# QuantumPCB_V1_0.net
KiCad netlist of a schematic drawn in EAGLE
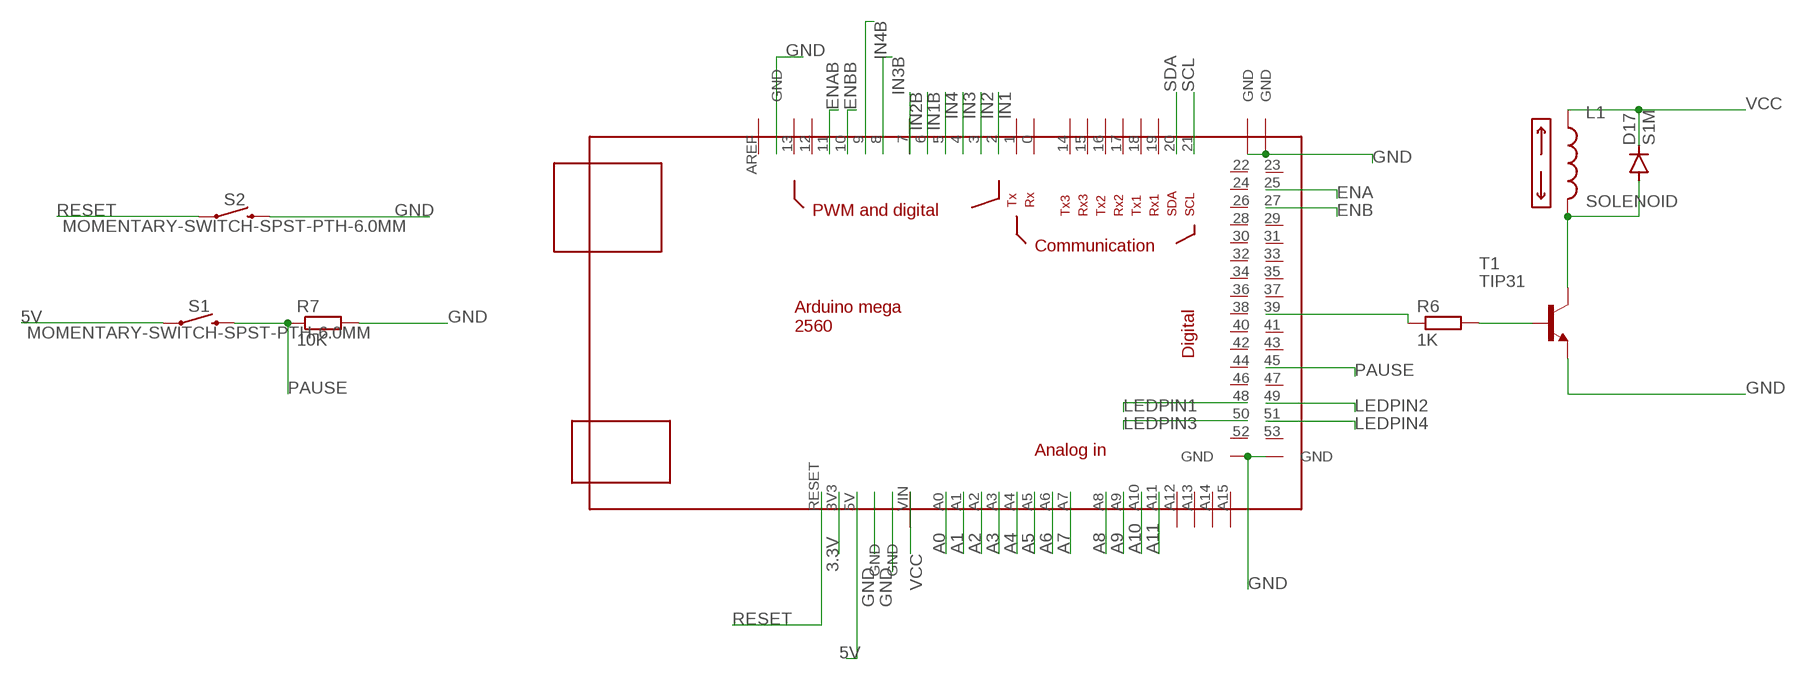
[diagram p0: schematic, sheet 1]
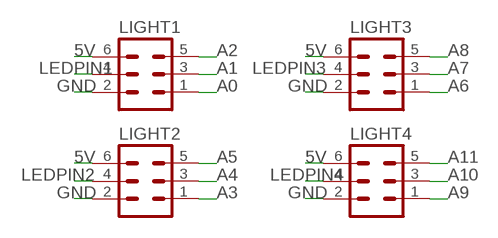
[diagram p1: schematic, sheet 2]
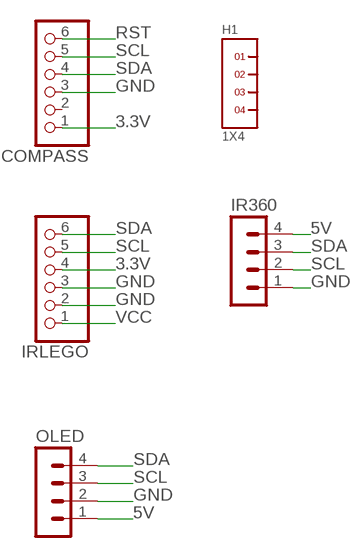
[diagram p2: schematic, sheet 3]
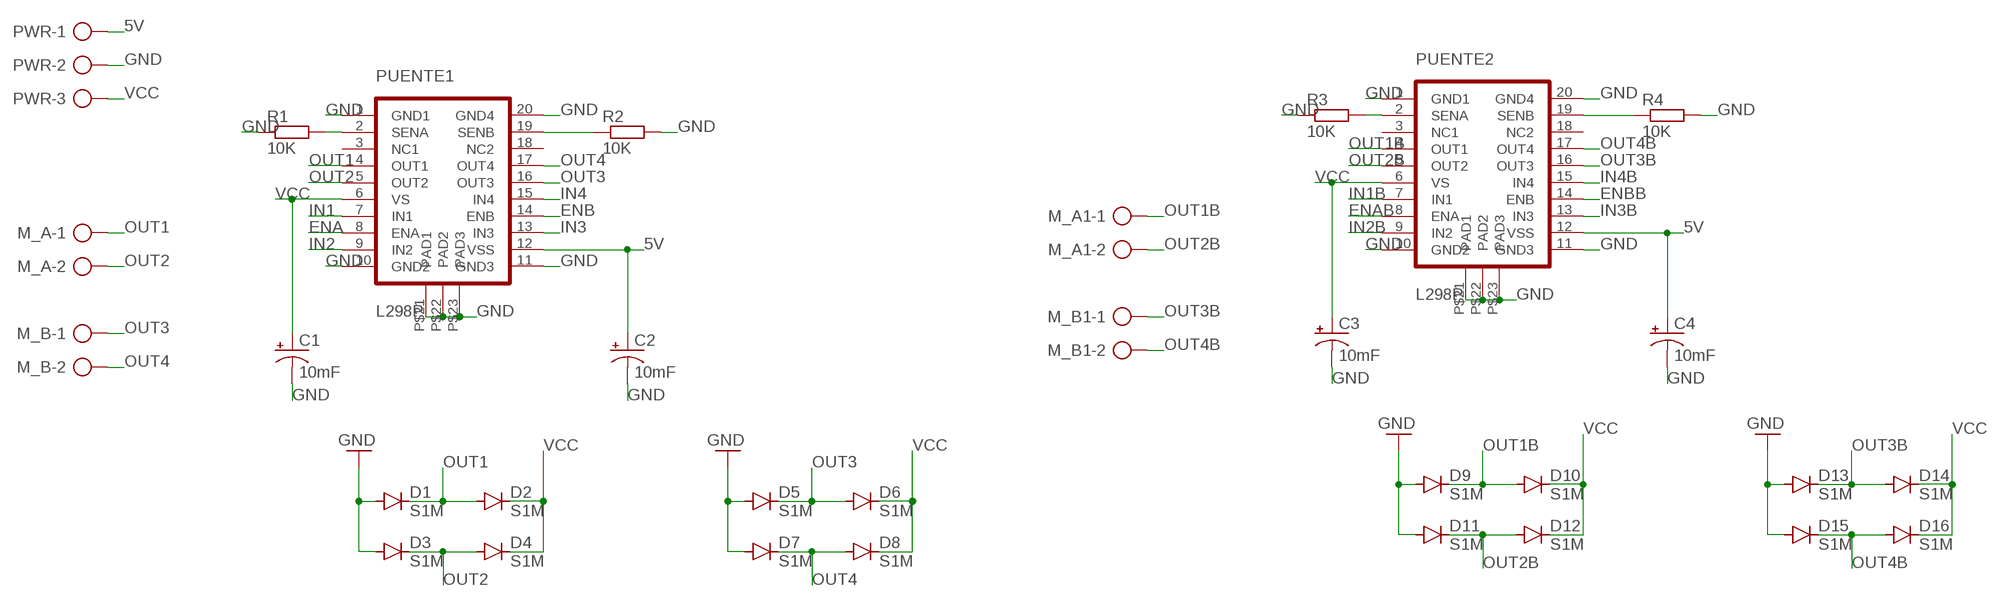
[diagram p3: schematic, sheet 4]

(export (version "E")
  (design (tool "Eeschema 10.0.6"))
  (components
    (comp (ref "D17")
      (value "S1M")
      (footprint "eagle-import:SMA")
      (libsource (lib "eagle-import") (part "S1M"))
    )
    (comp (ref "L1")
      (value "SOLENOID")
      (footprint "eagle-import:1X02")
      (libsource (lib "eagle-import") (part "SOLENOID"))
    )
    (comp (ref "R6")
      (value "1K")
      (footprint "eagle-import:R0603")
      (libsource (lib "eagle-import") (part "R-EU_R0603"))
    )
    (comp (ref "R7")
      (value "10K")
      (footprint "eagle-import:R0603")
      (libsource (lib "eagle-import") (part "R-EU_R0603"))
    )
    (comp (ref "S1")
      (value "MOMENTARY-SWITCH-SPST-PTH-6.0MM")
      (footprint "eagle-import:TACTILE_SWITCH_PTH_6.0MM")
      (libsource (lib "eagle-import") (part "MOMENTARY-SWITCH-SPST-PTH-6.0MM"))
    )
    (comp (ref "S2")
      (value "MOMENTARY-SWITCH-SPST-PTH-6.0MM")
      (footprint "eagle-import:TACTILE_SWITCH_PTH_6.0MM")
      (libsource (lib "eagle-import") (part "MOMENTARY-SWITCH-SPST-PTH-6.0MM"))
    )
    (comp (ref "T1")
      (value "TIP31")
      (footprint "eagle-import:TO220")
      (libsource (lib "eagle-import") (part "TIP31"))
    )
    (comp (ref "U$1")
      (value "MEGA_DEVICE")
      (footprint "eagle-import:MEGAOUTLINE")
      (libsource (lib "eagle-import") (part "MEGA_DEVICE"))
    )
    (comp (ref "C1")
      (value "10mF")
      (footprint "eagle-import:E2-5")
      (libsource (lib "eagle-import") (part "CPOL-USE2-5"))
    )
    (comp (ref "C2")
      (value "10mF")
      (footprint "eagle-import:E2-5")
      (libsource (lib "eagle-import") (part "CPOL-USE2-5"))
    )
    (comp (ref "C3")
      (value "10mF")
      (footprint "eagle-import:E2-5")
      (libsource (lib "eagle-import") (part "CPOL-USE2-5"))
    )
    (comp (ref "C4")
      (value "10mF")
      (footprint "eagle-import:E2-5")
      (libsource (lib "eagle-import") (part "CPOL-USE2-5"))
    )
    (comp (ref "D1")
      (value "S1M")
      (footprint "eagle-import:SMA")
      (libsource (lib "eagle-import") (part "S1M"))
    )
    (comp (ref "D2")
      (value "S1M")
      (footprint "eagle-import:SMA")
      (libsource (lib "eagle-import") (part "S1M"))
    )
    (comp (ref "D3")
      (value "S1M")
      (footprint "eagle-import:SMA")
      (libsource (lib "eagle-import") (part "S1M"))
    )
    (comp (ref "D4")
      (value "S1M")
      (footprint "eagle-import:SMA")
      (libsource (lib "eagle-import") (part "S1M"))
    )
    (comp (ref "D5")
      (value "S1M")
      (footprint "eagle-import:SMA")
      (libsource (lib "eagle-import") (part "S1M"))
    )
    (comp (ref "D6")
      (value "S1M")
      (footprint "eagle-import:SMA")
      (libsource (lib "eagle-import") (part "S1M"))
    )
    (comp (ref "D7")
      (value "S1M")
      (footprint "eagle-import:SMA")
      (libsource (lib "eagle-import") (part "S1M"))
    )
    (comp (ref "D8")
      (value "S1M")
      (footprint "eagle-import:SMA")
      (libsource (lib "eagle-import") (part "S1M"))
    )
    (comp (ref "D9")
      (value "S1M")
      (footprint "eagle-import:SMA")
      (libsource (lib "eagle-import") (part "S1M"))
    )
    (comp (ref "D10")
      (value "S1M")
      (footprint "eagle-import:SMA")
      (libsource (lib "eagle-import") (part "S1M"))
    )
    (comp (ref "D11")
      (value "S1M")
      (footprint "eagle-import:SMA")
      (libsource (lib "eagle-import") (part "S1M"))
    )
    (comp (ref "D12")
      (value "S1M")
      (footprint "eagle-import:SMA")
      (libsource (lib "eagle-import") (part "S1M"))
    )
    (comp (ref "D13")
      (value "S1M")
      (footprint "eagle-import:SMA")
      (libsource (lib "eagle-import") (part "S1M"))
    )
    (comp (ref "D14")
      (value "S1M")
      (footprint "eagle-import:SMA")
      (libsource (lib "eagle-import") (part "S1M"))
    )
    (comp (ref "D15")
      (value "S1M")
      (footprint "eagle-import:SMA")
      (libsource (lib "eagle-import") (part "S1M"))
    )
    (comp (ref "D16")
      (value "S1M")
      (footprint "eagle-import:SMA")
      (libsource (lib "eagle-import") (part "S1M"))
    )
    (comp (ref "M_A")
      (value "AK500/2")
      (footprint "eagle-import:AK500_2")
      (libsource (lib "eagle-import") (part "AK500/2"))
    )
    (comp (ref "M_A1")
      (value "AK500/2")
      (footprint "eagle-import:AK500_2")
      (libsource (lib "eagle-import") (part "AK500/2"))
    )
    (comp (ref "M_B")
      (value "AK500/2")
      (footprint "eagle-import:AK500_2")
      (libsource (lib "eagle-import") (part "AK500/2"))
    )
    (comp (ref "M_B1")
      (value "AK500/2")
      (footprint "eagle-import:AK500_2")
      (libsource (lib "eagle-import") (part "AK500/2"))
    )
    (comp (ref "PUENTE1")
      (value "L298P")
      (footprint "eagle-import:POWER-SO20")
      (fields (field (name "MF") "STMicroelectronics"))
      (libsource (lib "eagle-import") (part "L298P"))
    )
    (comp (ref "PUENTE2")
      (value "L298P")
      (footprint "eagle-import:POWER-SO20")
      (fields (field (name "MF") "STMicroelectronics"))
      (libsource (lib "eagle-import") (part "L298P"))
    )
    (comp (ref "PWR")
      (value "AK500/3")
      (footprint "eagle-import:AK500_3")
      (libsource (lib "eagle-import") (part "AK500/3"))
    )
    (comp (ref "R1")
      (value "10K")
      (footprint "eagle-import:R0603")
      (libsource (lib "eagle-import") (part "R-EU_R0603"))
    )
    (comp (ref "R2")
      (value "10K")
      (footprint "eagle-import:R0603")
      (libsource (lib "eagle-import") (part "R-EU_R0603"))
    )
    (comp (ref "R3")
      (value "10K")
      (footprint "eagle-import:R0603")
      (libsource (lib "eagle-import") (part "R-EU_R0603"))
    )
    (comp (ref "R4")
      (value "10K")
      (footprint "eagle-import:R0603")
      (libsource (lib "eagle-import") (part "R-EU_R0603"))
    )
    (comp (ref "LIGHT1")
      (value "MA03-2")
      (footprint "eagle-import:MA03-2")
      (libsource (lib "eagle-import") (part "MA03-2"))
    )
    (comp (ref "LIGHT2")
      (value "MA03-2")
      (footprint "eagle-import:MA03-2")
      (libsource (lib "eagle-import") (part "MA03-2"))
    )
    (comp (ref "LIGHT3")
      (value "MA03-2")
      (footprint "eagle-import:MA03-2")
      (libsource (lib "eagle-import") (part "MA03-2"))
    )
    (comp (ref "LIGHT4")
      (value "MA03-2")
      (footprint "eagle-import:MA03-2")
      (libsource (lib "eagle-import") (part "MA03-2"))
    )
    (comp (ref "COMPASS")
      (value "PINHD-1X6")
      (footprint "eagle-import:1X06")
      (libsource (lib "eagle-import") (part "PINHD-1X6"))
    )
    (comp (ref "H1")
      (value "1X4")
      (footprint "eagle-import:1X4")
      (libsource (lib "eagle-import") (part "1X4"))
    )
    (comp (ref "IR360")
      (value "MA04-1")
      (footprint "eagle-import:MA04-1")
      (libsource (lib "eagle-import") (part "MA04-1"))
    )
    (comp (ref "IRLEGO")
      (value "PINHD-1X6")
      (footprint "eagle-import:1X06")
      (libsource (lib "eagle-import") (part "PINHD-1X6"))
    )
    (comp (ref "OLED")
      (value "MA04-1")
      (footprint "eagle-import:MA04-1")
      (libsource (lib "eagle-import") (part "MA04-1"))
    )
  )
  (nets
    (net (code "1") (name "3.3V") (class "Default")
      (node (ref "COMPASS") (pin "1") (pinfunction "1_1") (pintype "passive"))
      (node (ref "IRLEGO") (pin "4") (pinfunction "4_4") (pintype "passive"))
      (node (ref "U$1") (pin "3V3") (pinfunction "3V3_3V3") (pintype "bidirectional"))
    )
    (net (code "2") (name "5V") (class "Default")
      (node (ref "C2") (pin "+") (pinfunction "+_+") (pintype "passive"))
      (node (ref "C4") (pin "+") (pinfunction "+_+") (pintype "passive"))
      (node (ref "IR360") (pin "4") (pinfunction "4_4") (pintype "passive"))
      (node (ref "LIGHT1") (pin "6") (pinfunction "6_6") (pintype "passive"))
      (node (ref "LIGHT2") (pin "6") (pinfunction "6_6") (pintype "passive"))
      (node (ref "LIGHT3") (pin "6") (pinfunction "6_6") (pintype "passive"))
      (node (ref "LIGHT4") (pin "6") (pinfunction "6_6") (pintype "passive"))
      (node (ref "OLED") (pin "1") (pinfunction "1_1") (pintype "passive"))
      (node (ref "PUENTE1") (pin "P$12") (pinfunction "VSS_P$12") (pintype "power_in"))
      (node (ref "PUENTE2") (pin "P$12") (pinfunction "VSS_P$12") (pintype "power_in"))
      (node (ref "PWR") (pin "1") (pinfunction "KL_1") (pintype "passive"))
      (node (ref "S1") (pin "1") (pinfunction "1_1") (pintype "passive"))
      (node (ref "U$1") (pin "5V") (pinfunction "5V_5V") (pintype "bidirectional"))
    )
    (net (code "3") (name "A0") (class "Default")
      (node (ref "LIGHT1") (pin "1") (pinfunction "1_1") (pintype "passive"))
      (node (ref "U$1") (pin "A0") (pinfunction "A0_A0") (pintype "bidirectional"))
    )
    (net (code "4") (name "A1") (class "Default")
      (node (ref "LIGHT1") (pin "3") (pinfunction "3_3") (pintype "passive"))
      (node (ref "U$1") (pin "A1") (pinfunction "A1_A1") (pintype "bidirectional"))
    )
    (net (code "5") (name "A2") (class "Default")
      (node (ref "LIGHT1") (pin "5") (pinfunction "5_5") (pintype "passive"))
      (node (ref "U$1") (pin "A2") (pinfunction "A2_A2") (pintype "bidirectional"))
    )
    (net (code "6") (name "A3") (class "Default")
      (node (ref "LIGHT2") (pin "1") (pinfunction "1_1") (pintype "passive"))
      (node (ref "U$1") (pin "A3") (pinfunction "A3_A3") (pintype "bidirectional"))
    )
    (net (code "7") (name "A4") (class "Default")
      (node (ref "LIGHT2") (pin "3") (pinfunction "3_3") (pintype "passive"))
      (node (ref "U$1") (pin "A4") (pinfunction "A4_A4") (pintype "bidirectional"))
    )
    (net (code "8") (name "A5") (class "Default")
      (node (ref "LIGHT2") (pin "5") (pinfunction "5_5") (pintype "passive"))
      (node (ref "U$1") (pin "A5") (pinfunction "A5_A5") (pintype "bidirectional"))
    )
    (net (code "9") (name "A6") (class "Default")
      (node (ref "LIGHT3") (pin "1") (pinfunction "1_1") (pintype "passive"))
      (node (ref "U$1") (pin "A6") (pinfunction "A6_A6") (pintype "bidirectional"))
    )
    (net (code "10") (name "A7") (class "Default")
      (node (ref "LIGHT3") (pin "3") (pinfunction "3_3") (pintype "passive"))
      (node (ref "U$1") (pin "A7") (pinfunction "A7_A7") (pintype "bidirectional"))
    )
    (net (code "11") (name "A8") (class "Default")
      (node (ref "LIGHT3") (pin "5") (pinfunction "5_5") (pintype "passive"))
      (node (ref "U$1") (pin "A8") (pinfunction "A8_A8") (pintype "bidirectional"))
    )
    (net (code "12") (name "A9") (class "Default")
      (node (ref "LIGHT4") (pin "1") (pinfunction "1_1") (pintype "passive"))
      (node (ref "U$1") (pin "A9") (pinfunction "A9_A9") (pintype "bidirectional"))
    )
    (net (code "13") (name "A10") (class "Default")
      (node (ref "LIGHT4") (pin "3") (pinfunction "3_3") (pintype "passive"))
      (node (ref "U$1") (pin "A10") (pinfunction "A10_A10") (pintype "bidirectional"))
    )
    (net (code "14") (name "A11") (class "Default")
      (node (ref "LIGHT4") (pin "5") (pinfunction "5_5") (pintype "passive"))
      (node (ref "U$1") (pin "A11") (pinfunction "A11_A11") (pintype "bidirectional"))
    )
    (net (code "15") (name "ENA") (class "Default")
      (node (ref "PUENTE1") (pin "P$8") (pinfunction "ENA_P$8") (pintype "input"))
      (node (ref "U$1") (pin "25") (pinfunction "25_25") (pintype "bidirectional"))
    )
    (net (code "16") (name "ENAB") (class "Default")
      (node (ref "PUENTE2") (pin "P$8") (pinfunction "ENA_P$8") (pintype "input"))
      (node (ref "U$1") (pin "11") (pinfunction "11_11") (pintype "bidirectional"))
    )
    (net (code "17") (name "ENB") (class "Default")
      (node (ref "PUENTE1") (pin "P$14") (pinfunction "ENB_P$14") (pintype "input"))
      (node (ref "U$1") (pin "27") (pinfunction "27_27") (pintype "bidirectional"))
    )
    (net (code "18") (name "ENBB") (class "Default")
      (node (ref "PUENTE2") (pin "P$14") (pinfunction "ENB_P$14") (pintype "input"))
      (node (ref "U$1") (pin "10") (pinfunction "10_10") (pintype "bidirectional"))
    )
    (net (code "19") (name "GND") (class "Default")
      (node (ref "C1") (pin "-") (pinfunction "-_-") (pintype "passive"))
      (node (ref "C2") (pin "-") (pinfunction "-_-") (pintype "passive"))
      (node (ref "C3") (pin "-") (pinfunction "-_-") (pintype "passive"))
      (node (ref "C4") (pin "-") (pinfunction "-_-") (pintype "passive"))
      (node (ref "COMPASS") (pin "3") (pinfunction "3_3") (pintype "passive"))
      (node (ref "D1") (pin "A") (pinfunction "A_A") (pintype "passive"))
      (node (ref "D11") (pin "A") (pinfunction "A_A") (pintype "passive"))
      (node (ref "D13") (pin "A") (pinfunction "A_A") (pintype "passive"))
      (node (ref "D15") (pin "A") (pinfunction "A_A") (pintype "passive"))
      (node (ref "D3") (pin "A") (pinfunction "A_A") (pintype "passive"))
      (node (ref "D5") (pin "A") (pinfunction "A_A") (pintype "passive"))
      (node (ref "D7") (pin "A") (pinfunction "A_A") (pintype "passive"))
      (node (ref "D9") (pin "A") (pinfunction "A_A") (pintype "passive"))
      (node (ref "IR360") (pin "1") (pinfunction "1_1") (pintype "passive"))
      (node (ref "IRLEGO") (pin "2") (pinfunction "2_2") (pintype "passive"))
      (node (ref "IRLEGO") (pin "3") (pinfunction "3_3") (pintype "passive"))
      (node (ref "LIGHT1") (pin "2") (pinfunction "2_2") (pintype "passive"))
      (node (ref "LIGHT2") (pin "2") (pinfunction "2_2") (pintype "passive"))
      (node (ref "LIGHT3") (pin "2") (pinfunction "2_2") (pintype "passive"))
      (node (ref "LIGHT4") (pin "2") (pinfunction "2_2") (pintype "passive"))
      (node (ref "OLED") (pin "2") (pinfunction "2_2") (pintype "passive"))
      (node (ref "PUENTE1") (pin "P$1") (pinfunction "GND1_P$1") (pintype "power_in"))
      (node (ref "PUENTE1") (pin "P$10") (pinfunction "GND2_P$10") (pintype "power_in"))
      (node (ref "PUENTE1") (pin "P$11") (pinfunction "GND3_P$11") (pintype "power_in"))
      (node (ref "PUENTE1") (pin "P$20") (pinfunction "GND4_P$20") (pintype "power_in"))
      (node (ref "PUENTE1") (pin "P$21") (pinfunction "PAD1_P$21") (pintype "passive"))
      (node (ref "PUENTE1") (pin "P$22") (pinfunction "PAD2_P$22") (pintype "passive"))
      (node (ref "PUENTE1") (pin "P$23") (pinfunction "PAD3_P$23") (pintype "passive"))
      (node (ref "PUENTE2") (pin "P$1") (pinfunction "GND1_P$1") (pintype "power_in"))
      (node (ref "PUENTE2") (pin "P$10") (pinfunction "GND2_P$10") (pintype "power_in"))
      (node (ref "PUENTE2") (pin "P$11") (pinfunction "GND3_P$11") (pintype "power_in"))
      (node (ref "PUENTE2") (pin "P$20") (pinfunction "GND4_P$20") (pintype "power_in"))
      (node (ref "PUENTE2") (pin "P$21") (pinfunction "PAD1_P$21") (pintype "passive"))
      (node (ref "PUENTE2") (pin "P$22") (pinfunction "PAD2_P$22") (pintype "passive"))
      (node (ref "PUENTE2") (pin "P$23") (pinfunction "PAD3_P$23") (pintype "passive"))
      (node (ref "PWR") (pin "2") (pinfunction "KL_2") (pintype "passive"))
      (node (ref "R1") (pin "1") (pinfunction "1_1") (pintype "passive"))
      (node (ref "R2") (pin "2") (pinfunction "2_2") (pintype "passive"))
      (node (ref "R3") (pin "1") (pinfunction "1_1") (pintype "passive"))
      (node (ref "R4") (pin "2") (pinfunction "2_2") (pintype "passive"))
      (node (ref "R7") (pin "2") (pinfunction "2_2") (pintype "passive"))
      (node (ref "S2") (pin "3") (pinfunction "2_3") (pintype "passive"))
      (node (ref "T1") (pin "3") (pinfunction "E_3") (pintype "passive"))
      (node (ref "U$1") (pin "GND@1") (pinfunction "GND_GND@1") (pintype "bidirectional"))
      (node (ref "U$1") (pin "GND@2") (pinfunction "GND_GND@2") (pintype "bidirectional"))
      (node (ref "U$1") (pin "GND@3") (pinfunction "GND_GND@3") (pintype "bidirectional"))
      (node (ref "U$1") (pin "GND@4") (pinfunction "GND_GND@4") (pintype "bidirectional"))
      (node (ref "U$1") (pin "GND@5") (pinfunction "GND_GND@5") (pintype "bidirectional"))
      (node (ref "U$1") (pin "GND@6") (pinfunction "GND_GND@6") (pintype "bidirectional"))
      (node (ref "U$1") (pin "GND@7") (pinfunction "GND_GND@7") (pintype "bidirectional"))
    )
    (net (code "20") (name "IN1") (class "Default")
      (node (ref "PUENTE1") (pin "P$7") (pinfunction "IN1_P$7") (pintype "input"))
      (node (ref "U$1") (pin "2") (pinfunction "2_2") (pintype "bidirectional"))
    )
    (net (code "21") (name "IN1B") (class "Default")
      (node (ref "PUENTE2") (pin "P$7") (pinfunction "IN1_P$7") (pintype "input"))
      (node (ref "U$1") (pin "6") (pinfunction "6_6") (pintype "bidirectional"))
    )
    (net (code "22") (name "IN2") (class "Default")
      (node (ref "PUENTE1") (pin "P$9") (pinfunction "IN2_P$9") (pintype "input"))
      (node (ref "U$1") (pin "3") (pinfunction "3_3") (pintype "bidirectional"))
    )
    (net (code "23") (name "IN2B") (class "Default")
      (node (ref "PUENTE2") (pin "P$9") (pinfunction "IN2_P$9") (pintype "input"))
      (node (ref "U$1") (pin "7") (pinfunction "7_7") (pintype "bidirectional"))
    )
    (net (code "24") (name "IN3") (class "Default")
      (node (ref "PUENTE1") (pin "P$13") (pinfunction "IN3_P$13") (pintype "input"))
      (node (ref "U$1") (pin "4") (pinfunction "4_4") (pintype "bidirectional"))
    )
    (net (code "25") (name "IN3B") (class "Default")
      (node (ref "PUENTE2") (pin "P$13") (pinfunction "IN3_P$13") (pintype "input"))
      (node (ref "U$1") (pin "8") (pinfunction "8_8") (pintype "bidirectional"))
    )
    (net (code "26") (name "IN4") (class "Default")
      (node (ref "PUENTE1") (pin "P$15") (pinfunction "IN4_P$15") (pintype "input"))
      (node (ref "U$1") (pin "5") (pinfunction "5_5") (pintype "bidirectional"))
    )
    (net (code "27") (name "IN4B") (class "Default")
      (node (ref "PUENTE2") (pin "P$15") (pinfunction "IN4_P$15") (pintype "input"))
      (node (ref "U$1") (pin "9") (pinfunction "9_9") (pintype "bidirectional"))
    )
    (net (code "28") (name "LEDPIN1") (class "Default")
      (node (ref "LIGHT1") (pin "4") (pinfunction "4_4") (pintype "passive"))
      (node (ref "U$1") (pin "48") (pinfunction "48_48") (pintype "bidirectional"))
    )
    (net (code "29") (name "LEDPIN2") (class "Default")
      (node (ref "LIGHT2") (pin "4") (pinfunction "4_4") (pintype "passive"))
      (node (ref "U$1") (pin "49") (pinfunction "49_49") (pintype "bidirectional"))
    )
    (net (code "30") (name "LEDPIN3") (class "Default")
      (node (ref "LIGHT3") (pin "4") (pinfunction "4_4") (pintype "passive"))
      (node (ref "U$1") (pin "50") (pinfunction "50_50") (pintype "bidirectional"))
    )
    (net (code "31") (name "LEDPIN4") (class "Default")
      (node (ref "LIGHT4") (pin "4") (pinfunction "4_4") (pintype "passive"))
      (node (ref "U$1") (pin "51") (pinfunction "51_51") (pintype "bidirectional"))
    )
    (net (code "32") (name "Net-(PUENTE1-SENA)") (class "Default")
      (node (ref "PUENTE1") (pin "P$2") (pinfunction "SENA_P$2") (pintype "input"))
      (node (ref "R1") (pin "2") (pinfunction "2_2") (pintype "passive"))
    )
    (net (code "33") (name "Net-(PUENTE1-SENB)") (class "Default")
      (node (ref "PUENTE1") (pin "P$19") (pinfunction "SENB_P$19") (pintype "input"))
      (node (ref "R2") (pin "1") (pinfunction "1_1") (pintype "passive"))
    )
    (net (code "34") (name "Net-(PUENTE2-SENA)") (class "Default")
      (node (ref "PUENTE2") (pin "P$2") (pinfunction "SENA_P$2") (pintype "input"))
      (node (ref "R3") (pin "2") (pinfunction "2_2") (pintype "passive"))
    )
    (net (code "35") (name "Net-(PUENTE2-SENB)") (class "Default")
      (node (ref "PUENTE2") (pin "P$19") (pinfunction "SENB_P$19") (pintype "input"))
      (node (ref "R4") (pin "1") (pinfunction "1_1") (pintype "passive"))
    )
    (net (code "36") (name "Net-(R6-Pad1)") (class "Default")
      (node (ref "R6") (pin "1") (pinfunction "1_1") (pintype "passive"))
      (node (ref "U$1") (pin "39") (pinfunction "39_39") (pintype "bidirectional"))
    )
    (net (code "37") (name "Net-(T1-B)") (class "Default")
      (node (ref "R6") (pin "2") (pinfunction "2_2") (pintype "passive"))
      (node (ref "T1") (pin "1") (pinfunction "B_1") (pintype "passive"))
    )
    (net (code "38") (name "Net-(T1-C)") (class "Default")
      (node (ref "D17") (pin "A") (pinfunction "A_A") (pintype "passive"))
      (node (ref "L1") (pin "2") (pinfunction "2_2") (pintype "passive"))
      (node (ref "T1") (pin "2") (pinfunction "C_2") (pintype "passive"))
    )
    (net (code "39") (name "OUT1") (class "Default")
      (node (ref "D1") (pin "C") (pinfunction "C_C") (pintype "passive"))
      (node (ref "D2") (pin "A") (pinfunction "A_A") (pintype "passive"))
      (node (ref "M_A") (pin "1") (pinfunction "KL_1") (pintype "passive"))
      (node (ref "PUENTE1") (pin "P$4") (pinfunction "OUT1_P$4") (pintype "output"))
    )
    (net (code "40") (name "OUT1B") (class "Default")
      (node (ref "D10") (pin "A") (pinfunction "A_A") (pintype "passive"))
      (node (ref "D9") (pin "C") (pinfunction "C_C") (pintype "passive"))
      (node (ref "M_A1") (pin "1") (pinfunction "KL_1") (pintype "passive"))
      (node (ref "PUENTE2") (pin "P$4") (pinfunction "OUT1_P$4") (pintype "output"))
    )
    (net (code "41") (name "OUT2") (class "Default")
      (node (ref "D3") (pin "C") (pinfunction "C_C") (pintype "passive"))
      (node (ref "D4") (pin "A") (pinfunction "A_A") (pintype "passive"))
      (node (ref "M_A") (pin "2") (pinfunction "KL_2") (pintype "passive"))
      (node (ref "PUENTE1") (pin "P$5") (pinfunction "OUT2_P$5") (pintype "output"))
    )
    (net (code "42") (name "OUT2B") (class "Default")
      (node (ref "D11") (pin "C") (pinfunction "C_C") (pintype "passive"))
      (node (ref "D12") (pin "A") (pinfunction "A_A") (pintype "passive"))
      (node (ref "M_A1") (pin "2") (pinfunction "KL_2") (pintype "passive"))
      (node (ref "PUENTE2") (pin "P$5") (pinfunction "OUT2_P$5") (pintype "output"))
    )
    (net (code "43") (name "OUT3") (class "Default")
      (node (ref "D5") (pin "C") (pinfunction "C_C") (pintype "passive"))
      (node (ref "D6") (pin "A") (pinfunction "A_A") (pintype "passive"))
      (node (ref "M_B") (pin "1") (pinfunction "KL_1") (pintype "passive"))
      (node (ref "PUENTE1") (pin "P$16") (pinfunction "OUT3_P$16") (pintype "output"))
    )
    (net (code "44") (name "OUT3B") (class "Default")
      (node (ref "D13") (pin "C") (pinfunction "C_C") (pintype "passive"))
      (node (ref "D14") (pin "A") (pinfunction "A_A") (pintype "passive"))
      (node (ref "M_B1") (pin "1") (pinfunction "KL_1") (pintype "passive"))
      (node (ref "PUENTE2") (pin "P$16") (pinfunction "OUT3_P$16") (pintype "output"))
    )
    (net (code "45") (name "OUT4") (class "Default")
      (node (ref "D7") (pin "C") (pinfunction "C_C") (pintype "passive"))
      (node (ref "D8") (pin "A") (pinfunction "A_A") (pintype "passive"))
      (node (ref "M_B") (pin "2") (pinfunction "KL_2") (pintype "passive"))
      (node (ref "PUENTE1") (pin "P$17") (pinfunction "OUT4_P$17") (pintype "output"))
    )
    (net (code "46") (name "OUT4B") (class "Default")
      (node (ref "D15") (pin "C") (pinfunction "C_C") (pintype "passive"))
      (node (ref "D16") (pin "A") (pinfunction "A_A") (pintype "passive"))
      (node (ref "M_B1") (pin "2") (pinfunction "KL_2") (pintype "passive"))
      (node (ref "PUENTE2") (pin "P$17") (pinfunction "OUT4_P$17") (pintype "output"))
    )
    (net (code "47") (name "PAUSE") (class "Default")
      (node (ref "R7") (pin "1") (pinfunction "1_1") (pintype "passive"))
      (node (ref "S1") (pin "3") (pinfunction "2_3") (pintype "passive"))
      (node (ref "U$1") (pin "45") (pinfunction "45_45") (pintype "bidirectional"))
    )
    (net (code "48") (name "RESET") (class "Default")
      (node (ref "S2") (pin "1") (pinfunction "1_1") (pintype "passive"))
      (node (ref "U$1") (pin "RESET") (pinfunction "RESET_RESET") (pintype "bidirectional"))
    )
    (net (code "49") (name "RST") (class "Default")
      (node (ref "COMPASS") (pin "6") (pinfunction "6_6") (pintype "passive"))
    )
    (net (code "50") (name "SCL") (class "Default")
      (node (ref "COMPASS") (pin "5") (pinfunction "5_5") (pintype "passive"))
      (node (ref "IR360") (pin "2") (pinfunction "2_2") (pintype "passive"))
      (node (ref "IRLEGO") (pin "5") (pinfunction "5_5") (pintype "passive"))
      (node (ref "OLED") (pin "3") (pinfunction "3_3") (pintype "passive"))
      (node (ref "U$1") (pin "21") (pinfunction "21_21") (pintype "bidirectional"))
    )
    (net (code "51") (name "SDA") (class "Default")
      (node (ref "COMPASS") (pin "4") (pinfunction "4_4") (pintype "passive"))
      (node (ref "IR360") (pin "3") (pinfunction "3_3") (pintype "passive"))
      (node (ref "IRLEGO") (pin "6") (pinfunction "6_6") (pintype "passive"))
      (node (ref "OLED") (pin "4") (pinfunction "4_4") (pintype "passive"))
      (node (ref "U$1") (pin "20") (pinfunction "20_20") (pintype "bidirectional"))
    )
    (net (code "52") (name "VCC") (class "Default")
      (node (ref "C1") (pin "+") (pinfunction "+_+") (pintype "passive"))
      (node (ref "C3") (pin "+") (pinfunction "+_+") (pintype "passive"))
      (node (ref "D10") (pin "C") (pinfunction "C_C") (pintype "passive"))
      (node (ref "D12") (pin "C") (pinfunction "C_C") (pintype "passive"))
      (node (ref "D14") (pin "C") (pinfunction "C_C") (pintype "passive"))
      (node (ref "D16") (pin "C") (pinfunction "C_C") (pintype "passive"))
      (node (ref "D17") (pin "C") (pinfunction "C_C") (pintype "passive"))
      (node (ref "D2") (pin "C") (pinfunction "C_C") (pintype "passive"))
      (node (ref "D4") (pin "C") (pinfunction "C_C") (pintype "passive"))
      (node (ref "D6") (pin "C") (pinfunction "C_C") (pintype "passive"))
      (node (ref "D8") (pin "C") (pinfunction "C_C") (pintype "passive"))
      (node (ref "IRLEGO") (pin "1") (pinfunction "1_1") (pintype "passive"))
      (node (ref "L1") (pin "1") (pinfunction "1_1") (pintype "passive"))
      (node (ref "PUENTE1") (pin "P$6") (pinfunction "VS_P$6") (pintype "power_in"))
      (node (ref "PUENTE2") (pin "P$6") (pinfunction "VS_P$6") (pintype "power_in"))
      (node (ref "PWR") (pin "3") (pinfunction "KL_3") (pintype "passive"))
      (node (ref "U$1") (pin "VIN") (pinfunction "VIN_VIN") (pintype "bidirectional"))
    )
    (net (code "53") (name "unconnected-(COMPASS-Pad2)") (class "Default")
      (node (ref "COMPASS") (pin "2") (pinfunction "2_2") (pintype "passive"))
    )
    (net (code "54") (name "unconnected-(H1-Pad1)") (class "Default")
      (node (ref "H1") (pin "1") (pinfunction "1_1") (pintype "bidirectional"))
    )
    (net (code "55") (name "unconnected-(H1-Pad2)") (class "Default")
      (node (ref "H1") (pin "2") (pinfunction "2_2") (pintype "bidirectional"))
    )
    (net (code "56") (name "unconnected-(H1-Pad3)") (class "Default")
      (node (ref "H1") (pin "3") (pinfunction "3_3") (pintype "bidirectional"))
    )
    (net (code "57") (name "unconnected-(H1-Pad4)") (class "Default")
      (node (ref "H1") (pin "4") (pinfunction "4_4") (pintype "bidirectional"))
    )
    (net (code "58") (name "unconnected-(PUENTE1-NC1-PadP$3)") (class "Default")
      (node (ref "PUENTE1") (pin "P$3") (pinfunction "NC1_P$3") (pintype "no_connect"))
    )
    (net (code "59") (name "unconnected-(PUENTE1-NC2-PadP$18)") (class "Default")
      (node (ref "PUENTE1") (pin "P$18") (pinfunction "NC2_P$18") (pintype "no_connect"))
    )
    (net (code "60") (name "unconnected-(PUENTE2-NC1-PadP$3)") (class "Default")
      (node (ref "PUENTE2") (pin "P$3") (pinfunction "NC1_P$3") (pintype "no_connect"))
    )
    (net (code "61") (name "unconnected-(PUENTE2-NC2-PadP$18)") (class "Default")
      (node (ref "PUENTE2") (pin "P$18") (pinfunction "NC2_P$18") (pintype "no_connect"))
    )
    (net (code "62") (name "unconnected-(U$1-Pad0)") (class "Default")
      (node (ref "U$1") (pin "0") (pinfunction "0_0") (pintype "bidirectional"))
    )
    (net (code "63") (name "unconnected-(U$1-Pad1)") (class "Default")
      (node (ref "U$1") (pin "1") (pinfunction "1_1") (pintype "bidirectional"))
    )
    (net (code "64") (name "unconnected-(U$1-Pad12)") (class "Default")
      (node (ref "U$1") (pin "12") (pinfunction "12_12") (pintype "bidirectional"))
    )
    (net (code "65") (name "unconnected-(U$1-Pad13)") (class "Default")
      (node (ref "U$1") (pin "13") (pinfunction "13_13") (pintype "bidirectional"))
    )
    (net (code "66") (name "unconnected-(U$1-Pad14)") (class "Default")
      (node (ref "U$1") (pin "14") (pinfunction "14_14") (pintype "bidirectional"))
    )
    (net (code "67") (name "unconnected-(U$1-Pad15)") (class "Default")
      (node (ref "U$1") (pin "15") (pinfunction "15_15") (pintype "bidirectional"))
    )
    (net (code "68") (name "unconnected-(U$1-Pad16)") (class "Default")
      (node (ref "U$1") (pin "16") (pinfunction "16_16") (pintype "bidirectional"))
    )
    (net (code "69") (name "unconnected-(U$1-Pad17)") (class "Default")
      (node (ref "U$1") (pin "17") (pinfunction "17_17") (pintype "bidirectional"))
    )
    (net (code "70") (name "unconnected-(U$1-Pad18)") (class "Default")
      (node (ref "U$1") (pin "18") (pinfunction "18_18") (pintype "bidirectional"))
    )
    (net (code "71") (name "unconnected-(U$1-Pad19)") (class "Default")
      (node (ref "U$1") (pin "19") (pinfunction "19_19") (pintype "bidirectional"))
    )
    (net (code "72") (name "unconnected-(U$1-Pad22)") (class "Default")
      (node (ref "U$1") (pin "22") (pinfunction "22_22") (pintype "bidirectional"))
    )
    (net (code "73") (name "unconnected-(U$1-Pad23)") (class "Default")
      (node (ref "U$1") (pin "23") (pinfunction "23_23") (pintype "bidirectional"))
    )
    (net (code "74") (name "unconnected-(U$1-Pad24)") (class "Default")
      (node (ref "U$1") (pin "24") (pinfunction "24_24") (pintype "bidirectional"))
    )
    (net (code "75") (name "unconnected-(U$1-Pad26)") (class "Default")
      (node (ref "U$1") (pin "26") (pinfunction "26_26") (pintype "bidirectional"))
    )
    (net (code "76") (name "unconnected-(U$1-Pad28)") (class "Default")
      (node (ref "U$1") (pin "28") (pinfunction "28_28") (pintype "bidirectional"))
    )
    (net (code "77") (name "unconnected-(U$1-Pad29)") (class "Default")
      (node (ref "U$1") (pin "29") (pinfunction "29_29") (pintype "bidirectional"))
    )
    (net (code "78") (name "unconnected-(U$1-Pad30)") (class "Default")
      (node (ref "U$1") (pin "30") (pinfunction "30_30") (pintype "bidirectional"))
    )
    (net (code "79") (name "unconnected-(U$1-Pad31)") (class "Default")
      (node (ref "U$1") (pin "31") (pinfunction "31_31") (pintype "bidirectional"))
    )
    (net (code "80") (name "unconnected-(U$1-Pad32)") (class "Default")
      (node (ref "U$1") (pin "32") (pinfunction "32_32") (pintype "bidirectional"))
    )
    (net (code "81") (name "unconnected-(U$1-Pad33)") (class "Default")
      (node (ref "U$1") (pin "33") (pinfunction "33_33") (pintype "bidirectional"))
    )
    (net (code "82") (name "unconnected-(U$1-Pad34)") (class "Default")
      (node (ref "U$1") (pin "34") (pinfunction "34_34") (pintype "bidirectional"))
    )
    (net (code "83") (name "unconnected-(U$1-Pad35)") (class "Default")
      (node (ref "U$1") (pin "35") (pinfunction "35_35") (pintype "bidirectional"))
    )
    (net (code "84") (name "unconnected-(U$1-Pad36)") (class "Default")
      (node (ref "U$1") (pin "36") (pinfunction "36_36") (pintype "bidirectional"))
    )
    (net (code "85") (name "unconnected-(U$1-Pad37)") (class "Default")
      (node (ref "U$1") (pin "37") (pinfunction "37_37") (pintype "bidirectional"))
    )
    (net (code "86") (name "unconnected-(U$1-Pad38)") (class "Default")
      (node (ref "U$1") (pin "38") (pinfunction "38_38") (pintype "bidirectional"))
    )
    (net (code "87") (name "unconnected-(U$1-Pad40)") (class "Default")
      (node (ref "U$1") (pin "40") (pinfunction "40_40") (pintype "bidirectional"))
    )
    (net (code "88") (name "unconnected-(U$1-Pad41)") (class "Default")
      (node (ref "U$1") (pin "41") (pinfunction "41_41") (pintype "bidirectional"))
    )
    (net (code "89") (name "unconnected-(U$1-Pad42)") (class "Default")
      (node (ref "U$1") (pin "42") (pinfunction "42_42") (pintype "bidirectional"))
    )
    (net (code "90") (name "unconnected-(U$1-Pad43)") (class "Default")
      (node (ref "U$1") (pin "43") (pinfunction "43_43") (pintype "bidirectional"))
    )
    (net (code "91") (name "unconnected-(U$1-Pad44)") (class "Default")
      (node (ref "U$1") (pin "44") (pinfunction "44_44") (pintype "bidirectional"))
    )
    (net (code "92") (name "unconnected-(U$1-Pad46)") (class "Default")
      (node (ref "U$1") (pin "46") (pinfunction "46_46") (pintype "bidirectional"))
    )
    (net (code "93") (name "unconnected-(U$1-Pad47)") (class "Default")
      (node (ref "U$1") (pin "47") (pinfunction "47_47") (pintype "bidirectional"))
    )
    (net (code "94") (name "unconnected-(U$1-Pad52)") (class "Default")
      (node (ref "U$1") (pin "52") (pinfunction "52_52") (pintype "bidirectional"))
    )
    (net (code "95") (name "unconnected-(U$1-Pad53)") (class "Default")
      (node (ref "U$1") (pin "53") (pinfunction "53_53") (pintype "bidirectional"))
    )
    (net (code "96") (name "unconnected-(U$1-PadA12)") (class "Default")
      (node (ref "U$1") (pin "A12") (pinfunction "A12_A12") (pintype "bidirectional"))
    )
    (net (code "97") (name "unconnected-(U$1-PadA13)") (class "Default")
      (node (ref "U$1") (pin "A13") (pinfunction "A13_A13") (pintype "bidirectional"))
    )
    (net (code "98") (name "unconnected-(U$1-PadA14)") (class "Default")
      (node (ref "U$1") (pin "A14") (pinfunction "A14_A14") (pintype "bidirectional"))
    )
    (net (code "99") (name "unconnected-(U$1-PadA15)") (class "Default")
      (node (ref "U$1") (pin "A15") (pinfunction "A15_A15") (pintype "bidirectional"))
    )
    (net (code "100") (name "unconnected-(U$1-PadAREF)") (class "Default")
      (node (ref "U$1") (pin "AREF") (pinfunction "AREF_AREF") (pintype "bidirectional"))
    )
  )
)
